# Meishino_v12.net
KiCad netlist of a schematic drawn in EAGLE
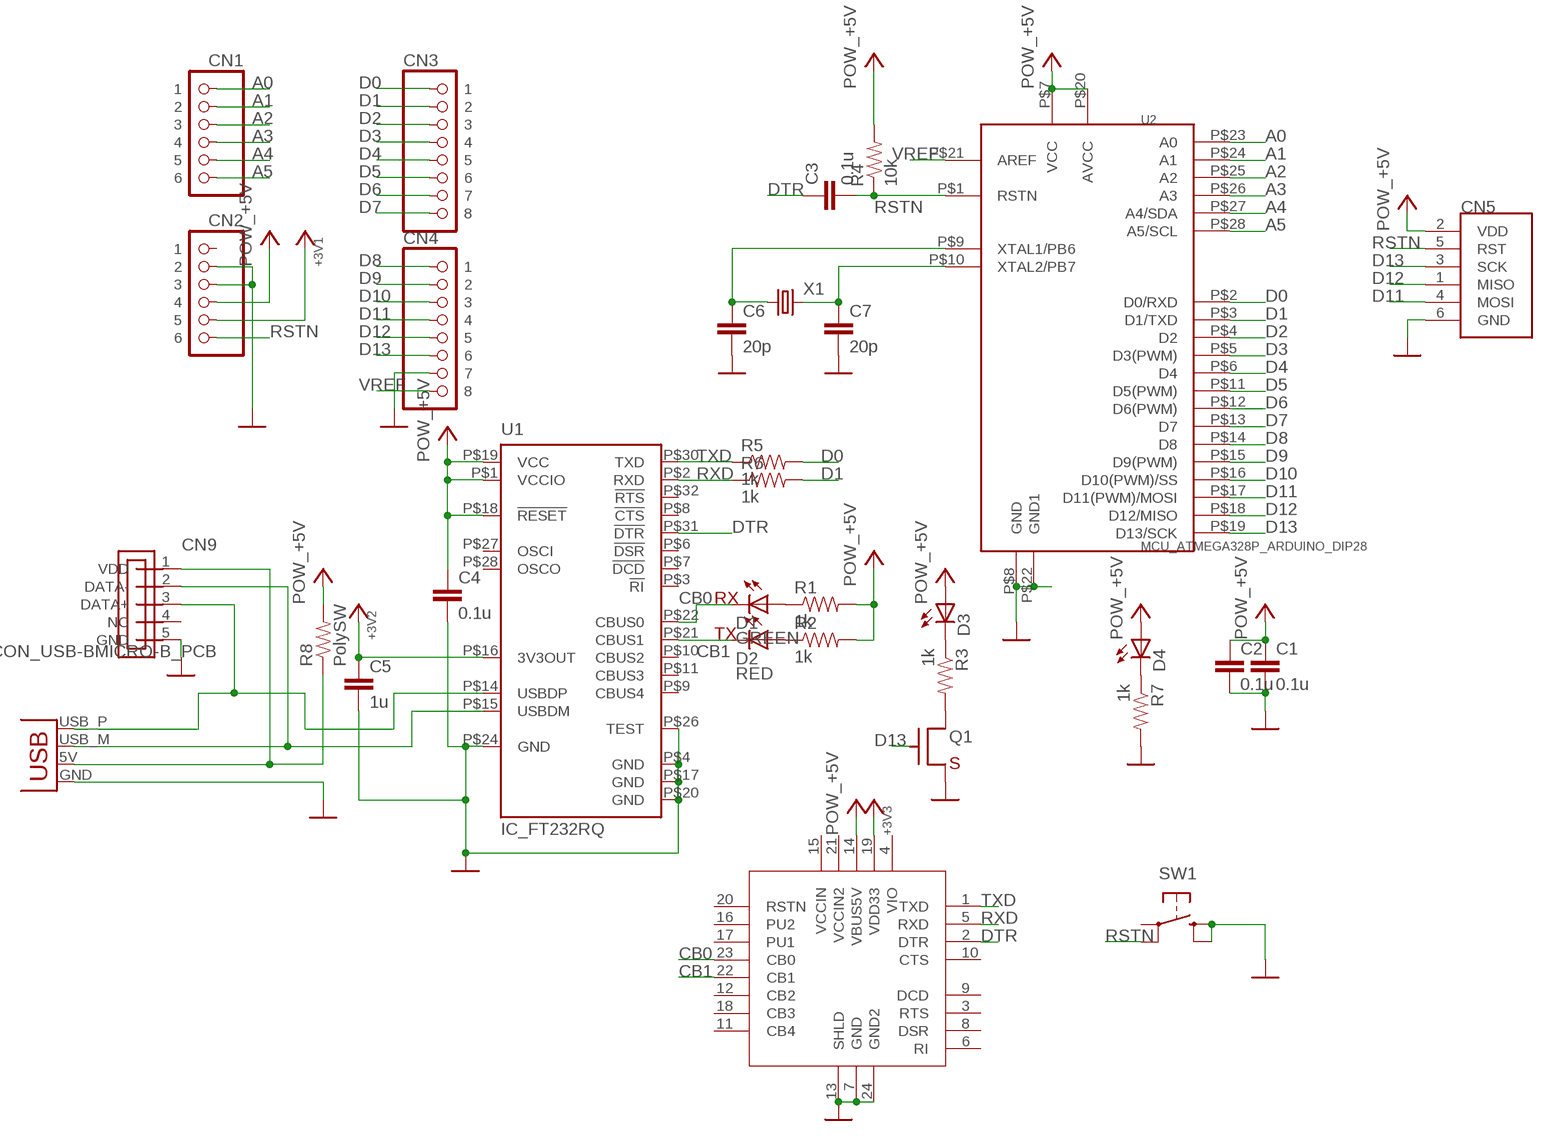
[diagram p0: schematic, sheet 1]

(export (version "E")
  (design (tool "Eeschema 10.0.6"))
  (components
    (comp (ref "C1")
      (value "0.1u")
      (footprint "eagle-import:CAP_TH_5MM_L")
      (libsource (lib "eagle-import") (part "CAPTH_5MML"))
    )
    (comp (ref "C2")
      (value "0.1u")
      (footprint "eagle-import:CAP_TH_5MM_L")
      (libsource (lib "eagle-import") (part "CAPTH_5MML"))
    )
    (comp (ref "C3")
      (value "0.1u")
      (footprint "eagle-import:CAP_TH_5MM_L")
      (libsource (lib "eagle-import") (part "CAPTH_5MML"))
    )
    (comp (ref "C4")
      (value "0.1u")
      (footprint "eagle-import:CAP_TH_5MM_L")
      (libsource (lib "eagle-import") (part "CAPTH_5MML"))
    )
    (comp (ref "C5")
      (value "1u")
      (footprint "eagle-import:CAP_TH_5MM_L")
      (libsource (lib "eagle-import") (part "CAPTH_5MML"))
    )
    (comp (ref "C6")
      (value "20p")
      (footprint "eagle-import:CAP_TH_5MM_L")
      (libsource (lib "eagle-import") (part "CAPTH_5MML"))
    )
    (comp (ref "C7")
      (value "20p")
      (footprint "eagle-import:CAP_TH_5MM_L")
      (libsource (lib "eagle-import") (part "CAPTH_5MML"))
    )
    (comp (ref "CN1")
      (value "CON_PINHD-1X6")
      (footprint "eagle-import:1X06")
      (libsource (lib "eagle-import") (part "CON_PINHD-1X6"))
    )
    (comp (ref "CN2")
      (value "CON_PINHD-1X6")
      (footprint "eagle-import:1X06")
      (libsource (lib "eagle-import") (part "CON_PINHD-1X6"))
    )
    (comp (ref "CN3")
      (value "CON_PINHD-1X8")
      (footprint "eagle-import:1X08")
      (libsource (lib "eagle-import") (part "CON_PINHD-1X8"))
    )
    (comp (ref "CN4")
      (value "CON_PINHD-1X8")
      (footprint "eagle-import:1X08")
      (libsource (lib "eagle-import") (part "CON_PINHD-1X8"))
    )
    (comp (ref "CN5")
      (value "CON_AVRISPTH")
      (footprint "eagle-import:2X03R")
      (libsource (lib "eagle-import") (part "CON_AVRISPTH"))
    )
    (comp (ref "CN9")
      (value "CON_USB-BMICRO-B_PCB")
      (footprint "eagle-import:USB-MICRO-PCB")
      (libsource (lib "eagle-import") (part "CON_USB-BMICRO-B_PCB"))
    )
    (comp (ref "D1")
      (value "GREEN")
      (footprint "eagle-import:SPARKFUN_LED5MM")
      (libsource (lib "eagle-import") (part "LED5MM"))
    )
    (comp (ref "D2")
      (value "RED")
      (footprint "eagle-import:SPARKFUN_LED5MM")
      (libsource (lib "eagle-import") (part "LED5MM"))
    )
    (comp (ref "D3")
      (value "LED5MM")
      (footprint "eagle-import:SPARKFUN_LED5MM")
      (libsource (lib "eagle-import") (part "LED5MM"))
    )
    (comp (ref "D4")
      (value "LED5MM")
      (footprint "eagle-import:SPARKFUN_LED5MM")
      (libsource (lib "eagle-import") (part "LED5MM"))
    )
    (comp (ref "JP2")
      (value "CON_USBPCB")
      (footprint "eagle-import:USB-A-PCB")
      (libsource (lib "eagle-import") (part "CON_USBPCB"))
    )
    (comp (ref "Q1")
      (value "TR_NMOS_2N7000")
      (footprint "eagle-import:TO-92")
      (libsource (lib "eagle-import") (part "TR_NMOS_2N7000"))
    )
    (comp (ref "R1")
      (value "1k")
      (footprint "eagle-import:R_TH_10MM_L")
      (libsource (lib "eagle-import") (part "RESTH_10MML"))
    )
    (comp (ref "R2")
      (value "1k")
      (footprint "eagle-import:R_TH_10MM_L")
      (libsource (lib "eagle-import") (part "RESTH_10MML"))
    )
    (comp (ref "R3")
      (value "1k")
      (footprint "eagle-import:R_TH_10MM_L")
      (libsource (lib "eagle-import") (part "RESTH_10MML"))
    )
    (comp (ref "R4")
      (value "10k")
      (footprint "eagle-import:R_TH_10MM_L")
      (libsource (lib "eagle-import") (part "RESTH_10MML"))
    )
    (comp (ref "R5")
      (value "1k")
      (footprint "eagle-import:R_TH_10MM_L")
      (libsource (lib "eagle-import") (part "RESTH_10MML"))
    )
    (comp (ref "R6")
      (value "1k")
      (footprint "eagle-import:R_TH_10MM_L")
      (libsource (lib "eagle-import") (part "RESTH_10MML"))
    )
    (comp (ref "R7")
      (value "1k")
      (footprint "eagle-import:R_TH_10MM_L")
      (libsource (lib "eagle-import") (part "RESTH_10MML"))
    )
    (comp (ref "R8")
      (value "PolySW")
      (footprint "eagle-import:R_TH_10MM_L")
      (libsource (lib "eagle-import") (part "RESTH_10MML"))
    )
    (comp (ref "SW1")
      (value "SW_TACTTH")
      (footprint "eagle-import:SW_B3F-10XX")
      (fields (field (name "MPN") "B3F-1000"))
      (libsource (lib "eagle-import") (part "SW_TACTTH"))
    )
    (comp (ref "U1")
      (value "IC_FT232RQ")
      (footprint "eagle-import:QFN32")
      (libsource (lib "eagle-import") (part "IC_FT232RQ"))
    )
    (comp (ref "U2")
      (value "MCU_ATMEGA328P_ARDUINO_DIP28")
      (footprint "eagle-import:DIP-28P(300MIL)")
      (libsource (lib "eagle-import") (part "MCU_ATMEGA328P_ARDUINO_DIP28"))
    )
    (comp (ref "U3")
      (value "MOD_AE_FT232_DIP24")
      (footprint "eagle-import:DIP24_600MIL")
      (libsource (lib "eagle-import") (part "MOD_AE_FT232_DIP24"))
    )
    (comp (ref "X1")
      (value "XTAL2HC49US")
      (footprint "eagle-import:HC49US")
      (libsource (lib "eagle-import") (part "XTAL2HC49US"))
    )
  )
  (nets
    (net (code "1") (name "/A0") (class "Default")
      (node (ref "CN1") (pin "1") (pinfunction "1_1") (pintype "passive"))
      (node (ref "U2") (pin "P$23") (pinfunction "A0_P$23") (pintype "bidirectional"))
    )
    (net (code "2") (name "/A1") (class "Default")
      (node (ref "CN1") (pin "2") (pinfunction "2_2") (pintype "passive"))
      (node (ref "U2") (pin "P$24") (pinfunction "A1_P$24") (pintype "bidirectional"))
    )
    (net (code "3") (name "/A2") (class "Default")
      (node (ref "CN1") (pin "3") (pinfunction "3_3") (pintype "passive"))
      (node (ref "U2") (pin "P$25") (pinfunction "A2_P$25") (pintype "bidirectional"))
    )
    (net (code "4") (name "/A3") (class "Default")
      (node (ref "CN1") (pin "4") (pinfunction "4_4") (pintype "passive"))
      (node (ref "U2") (pin "P$26") (pinfunction "A3_P$26") (pintype "bidirectional"))
    )
    (net (code "5") (name "/A4") (class "Default")
      (node (ref "CN1") (pin "5") (pinfunction "5_5") (pintype "passive"))
      (node (ref "U2") (pin "P$27") (pinfunction "A4/SDA_P$27") (pintype "bidirectional"))
    )
    (net (code "6") (name "/A5") (class "Default")
      (node (ref "CN1") (pin "6") (pinfunction "6_6") (pintype "passive"))
      (node (ref "U2") (pin "P$28") (pinfunction "A5/SCL_P$28") (pintype "bidirectional"))
    )
    (net (code "7") (name "/CB0") (class "Default")
      (node (ref "D1") (pin "K") (pinfunction "C_K") (pintype "passive"))
      (node (ref "U1") (pin "P$22") (pinfunction "CBUS0_P$22") (pintype "bidirectional"))
      (node (ref "U3") (pin "23") (pinfunction "CB0_23") (pintype "bidirectional"))
    )
    (net (code "8") (name "/CB1") (class "Default")
      (node (ref "D2") (pin "K") (pinfunction "C_K") (pintype "passive"))
      (node (ref "U1") (pin "P$21") (pinfunction "CBUS1_P$21") (pintype "bidirectional"))
      (node (ref "U3") (pin "22") (pinfunction "CB1_22") (pintype "bidirectional"))
    )
    (net (code "9") (name "/D0") (class "Default")
      (node (ref "CN3") (pin "1") (pinfunction "1_1") (pintype "passive"))
      (node (ref "R5") (pin "2") (pinfunction "2_2") (pintype "passive"))
      (node (ref "U2") (pin "P$2") (pinfunction "D0/RXD_P$2") (pintype "bidirectional"))
    )
    (net (code "10") (name "/D1") (class "Default")
      (node (ref "CN3") (pin "2") (pinfunction "2_2") (pintype "passive"))
      (node (ref "R6") (pin "2") (pinfunction "2_2") (pintype "passive"))
      (node (ref "U2") (pin "P$3") (pinfunction "D1/TXD_P$3") (pintype "bidirectional"))
    )
    (net (code "11") (name "/D2") (class "Default")
      (node (ref "CN3") (pin "3") (pinfunction "3_3") (pintype "passive"))
      (node (ref "U2") (pin "P$4") (pinfunction "D2_P$4") (pintype "bidirectional"))
    )
    (net (code "12") (name "/D3") (class "Default")
      (node (ref "CN3") (pin "4") (pinfunction "4_4") (pintype "passive"))
      (node (ref "U2") (pin "P$5") (pinfunction "D3(PWM)_P$5") (pintype "bidirectional"))
    )
    (net (code "13") (name "/D4") (class "Default")
      (node (ref "CN3") (pin "5") (pinfunction "5_5") (pintype "passive"))
      (node (ref "U2") (pin "P$6") (pinfunction "D4_P$6") (pintype "bidirectional"))
    )
    (net (code "14") (name "/D5") (class "Default")
      (node (ref "CN3") (pin "6") (pinfunction "6_6") (pintype "passive"))
      (node (ref "U2") (pin "P$11") (pinfunction "D5(PWM)_P$11") (pintype "bidirectional"))
    )
    (net (code "15") (name "/D6") (class "Default")
      (node (ref "CN3") (pin "7") (pinfunction "7_7") (pintype "passive"))
      (node (ref "U2") (pin "P$12") (pinfunction "D6(PWM)_P$12") (pintype "bidirectional"))
    )
    (net (code "16") (name "/D7") (class "Default")
      (node (ref "CN3") (pin "8") (pinfunction "8_8") (pintype "passive"))
      (node (ref "U2") (pin "P$13") (pinfunction "D7_P$13") (pintype "bidirectional"))
    )
    (net (code "17") (name "/D8") (class "Default")
      (node (ref "CN4") (pin "1") (pinfunction "1_1") (pintype "passive"))
      (node (ref "U2") (pin "P$14") (pinfunction "D8_P$14") (pintype "bidirectional"))
    )
    (net (code "18") (name "/D9") (class "Default")
      (node (ref "CN4") (pin "2") (pinfunction "2_2") (pintype "passive"))
      (node (ref "U2") (pin "P$15") (pinfunction "D9(PWM)_P$15") (pintype "bidirectional"))
    )
    (net (code "19") (name "/D10") (class "Default")
      (node (ref "CN4") (pin "3") (pinfunction "3_3") (pintype "passive"))
      (node (ref "U2") (pin "P$16") (pinfunction "D10(PWM)/SS_P$16") (pintype "bidirectional"))
    )
    (net (code "20") (name "/D11") (class "Default")
      (node (ref "CN4") (pin "4") (pinfunction "4_4") (pintype "passive"))
      (node (ref "CN5") (pin "4") (pinfunction "MOSI_4") (pintype "bidirectional"))
      (node (ref "U2") (pin "P$17") (pinfunction "D11(PWM)/MOSI_P$17") (pintype "bidirectional"))
    )
    (net (code "21") (name "/D12") (class "Default")
      (node (ref "CN4") (pin "5") (pinfunction "5_5") (pintype "passive"))
      (node (ref "CN5") (pin "1") (pinfunction "MISO_1") (pintype "bidirectional"))
      (node (ref "U2") (pin "P$18") (pinfunction "D12/MISO_P$18") (pintype "bidirectional"))
    )
    (net (code "22") (name "/D13") (class "Default")
      (node (ref "CN4") (pin "6") (pinfunction "6_6") (pintype "passive"))
      (node (ref "CN5") (pin "3") (pinfunction "SCK_3") (pintype "bidirectional"))
      (node (ref "Q1") (pin "2") (pinfunction "G_2") (pintype "bidirectional"))
      (node (ref "U2") (pin "P$19") (pinfunction "D13/SCK_P$19") (pintype "bidirectional"))
    )
    (net (code "23") (name "/DTR") (class "Default")
      (node (ref "C3") (pin "1") (pinfunction "1_1") (pintype "passive"))
      (node (ref "U1") (pin "P$31") (pinfunction "~{DTR}_P$31") (pintype "output"))
      (node (ref "U3") (pin "2") (pinfunction "DTR_2") (pintype "bidirectional"))
    )
    (net (code "24") (name "/RSTN") (class "Default")
      (node (ref "C3") (pin "2") (pinfunction "2_2") (pintype "passive"))
      (node (ref "CN2") (pin "6") (pinfunction "6_6") (pintype "passive"))
      (node (ref "CN5") (pin "5") (pinfunction "RST_5") (pintype "bidirectional"))
      (node (ref "R4") (pin "1") (pinfunction "1_1") (pintype "passive"))
      (node (ref "SW1") (pin "4") (pinfunction "P1_4") (pintype "passive"))
      (node (ref "U2") (pin "P$1") (pinfunction "RSTN_P$1") (pintype "bidirectional"))
    )
    (net (code "25") (name "/RXD") (class "Default")
      (node (ref "R6") (pin "1") (pinfunction "1_1") (pintype "passive"))
      (node (ref "U1") (pin "P$2") (pinfunction "RXD_P$2") (pintype "input"))
      (node (ref "U3") (pin "5") (pinfunction "RXD_5") (pintype "bidirectional"))
    )
    (net (code "26") (name "/TXD") (class "Default")
      (node (ref "R5") (pin "1") (pinfunction "1_1") (pintype "passive"))
      (node (ref "U1") (pin "P$30") (pinfunction "TXD_P$30") (pintype "output"))
      (node (ref "U3") (pin "1") (pinfunction "TXD_1") (pintype "bidirectional"))
    )
    (net (code "27") (name "/VREF") (class "Default")
      (node (ref "CN4") (pin "8") (pinfunction "8_8") (pintype "passive"))
      (node (ref "U2") (pin "P$21") (pinfunction "AREF_P$21") (pintype "bidirectional"))
    )
    (net (code "28") (name "Net-(CN9-DATA+)") (class "Default")
      (node (ref "CN9") (pin "3") (pinfunction "DATA+_3") (pintype "bidirectional"))
      (node (ref "JP2") (pin "USB_P") (pinfunction "D+_USB_P") (pintype "bidirectional"))
      (node (ref "U1") (pin "P$14") (pinfunction "USBDP_P$14") (pintype "bidirectional"))
    )
    (net (code "29") (name "Net-(CN9-DATA-)") (class "Default")
      (node (ref "CN9") (pin "2") (pinfunction "DATA-_2") (pintype "bidirectional"))
      (node (ref "JP2") (pin "USB_M") (pinfunction "D-_USB_M") (pintype "bidirectional"))
      (node (ref "U1") (pin "P$15") (pinfunction "USBDM_P$15") (pintype "bidirectional"))
    )
    (net (code "30") (name "Net-(CN9-VDD)") (class "Default")
      (node (ref "CN9") (pin "1") (pinfunction "VDD_1") (pintype "power_in"))
      (node (ref "JP2") (pin "5V") (pinfunction "VBUS_5V") (pintype "bidirectional"))
      (node (ref "R8") (pin "1") (pinfunction "1_1") (pintype "passive"))
    )
    (net (code "31") (name "Net-(D1-PadA)") (class "Default")
      (node (ref "D1") (pin "A") (pinfunction "A_A") (pintype "passive"))
      (node (ref "R1") (pin "1") (pinfunction "1_1") (pintype "passive"))
    )
    (net (code "32") (name "Net-(D2-PadA)") (class "Default")
      (node (ref "D2") (pin "A") (pinfunction "A_A") (pintype "passive"))
      (node (ref "R2") (pin "1") (pinfunction "1_1") (pintype "passive"))
    )
    (net (code "33") (name "Net-(D3-C)") (class "Default")
      (node (ref "D3") (pin "K") (pinfunction "C_K") (pintype "passive"))
      (node (ref "R3") (pin "1") (pinfunction "1_1") (pintype "passive"))
    )
    (net (code "34") (name "Net-(D4-C)") (class "Default")
      (node (ref "D4") (pin "K") (pinfunction "C_K") (pintype "passive"))
      (node (ref "R7") (pin "1") (pinfunction "1_1") (pintype "passive"))
    )
    (net (code "35") (name "Net-(Q1-D)") (class "Default")
      (node (ref "Q1") (pin "3") (pinfunction "D_3") (pintype "bidirectional"))
      (node (ref "R3") (pin "2") (pinfunction "2_2") (pintype "passive"))
    )
    (net (code "36") (name "Net-(U2-XTAL1{slash}PB6)") (class "Default")
      (node (ref "C6") (pin "1") (pinfunction "1_1") (pintype "passive"))
      (node (ref "U2") (pin "P$9") (pinfunction "XTAL1/PB6_P$9") (pintype "bidirectional"))
      (node (ref "X1") (pin "1") (pinfunction "1_1") (pintype "passive"))
    )
    (net (code "37") (name "Net-(U2-XTAL2{slash}PB7)") (class "Default")
      (node (ref "C7") (pin "1") (pinfunction "1_1") (pintype "passive"))
      (node (ref "U2") (pin "P$10") (pinfunction "XTAL2/PB7_P$10") (pintype "bidirectional"))
      (node (ref "X1") (pin "2") (pinfunction "2_2") (pintype "passive"))
    )
    (net (code "38") (name "POW_+3V3") (class "Default")
      (node (ref "C5") (pin "1") (pinfunction "1_1") (pintype "passive"))
      (node (ref "CN2") (pin "5") (pinfunction "5_5") (pintype "passive"))
      (node (ref "U1") (pin "P$16") (pinfunction "3V3OUT_P$16") (pintype "output"))
      (node (ref "U3") (pin "19") (pinfunction "VDD33_19") (pintype "bidirectional"))
    )
    (net (code "39") (name "POW_+5V") (class "Default")
      (node (ref "C1") (pin "1") (pinfunction "1_1") (pintype "passive"))
      (node (ref "C2") (pin "1") (pinfunction "1_1") (pintype "passive"))
      (node (ref "C4") (pin "1") (pinfunction "1_1") (pintype "passive"))
      (node (ref "CN2") (pin "4") (pinfunction "4_4") (pintype "passive"))
      (node (ref "CN5") (pin "2") (pinfunction "VDD_2") (pintype "bidirectional"))
      (node (ref "D3") (pin "A") (pinfunction "A_A") (pintype "passive"))
      (node (ref "D4") (pin "A") (pinfunction "A_A") (pintype "passive"))
      (node (ref "R1") (pin "2") (pinfunction "2_2") (pintype "passive"))
      (node (ref "R2") (pin "2") (pinfunction "2_2") (pintype "passive"))
      (node (ref "R4") (pin "2") (pinfunction "2_2") (pintype "passive"))
      (node (ref "R8") (pin "2") (pinfunction "2_2") (pintype "passive"))
      (node (ref "U1") (pin "P$1") (pinfunction "VCCIO_P$1") (pintype "power_in"))
      (node (ref "U1") (pin "P$18") (pinfunction "~{RESET}_P$18") (pintype "input"))
      (node (ref "U1") (pin "P$19") (pinfunction "VCC_P$19") (pintype "power_in"))
      (node (ref "U2") (pin "P$20") (pinfunction "AVCC_P$20") (pintype "power_in"))
      (node (ref "U2") (pin "P$7") (pinfunction "VCC_P$7") (pintype "power_in"))
      (node (ref "U3") (pin "14") (pinfunction "VBUS5V_14") (pintype "bidirectional"))
    )
    (net (code "40") (name "POW_GND") (class "Default")
      (node (ref "C1") (pin "2") (pinfunction "2_2") (pintype "passive"))
      (node (ref "C2") (pin "2") (pinfunction "2_2") (pintype "passive"))
      (node (ref "C4") (pin "2") (pinfunction "2_2") (pintype "passive"))
      (node (ref "C5") (pin "2") (pinfunction "2_2") (pintype "passive"))
      (node (ref "C6") (pin "2") (pinfunction "2_2") (pintype "passive"))
      (node (ref "C7") (pin "2") (pinfunction "2_2") (pintype "passive"))
      (node (ref "CN2") (pin "2") (pinfunction "2_2") (pintype "passive"))
      (node (ref "CN2") (pin "3") (pinfunction "3_3") (pintype "passive"))
      (node (ref "CN4") (pin "7") (pinfunction "7_7") (pintype "passive"))
      (node (ref "CN5") (pin "6") (pinfunction "GND_6") (pintype "bidirectional"))
      (node (ref "CN9") (pin "5") (pinfunction "GND_5") (pintype "power_in"))
      (node (ref "JP2") (pin "GND") (pinfunction "GND_GND") (pintype "bidirectional"))
      (node (ref "Q1") (pin "1") (pinfunction "S_1") (pintype "bidirectional"))
      (node (ref "R7") (pin "2") (pinfunction "2_2") (pintype "passive"))
      (node (ref "SW1") (pin "1") (pinfunction "S_1") (pintype "passive"))
      (node (ref "SW1") (pin "2") (pinfunction "S1_2") (pintype "passive"))
      (node (ref "U1") (pin "P$17") (pinfunction "GND_P$17") (pintype "power_in"))
      (node (ref "U1") (pin "P$20") (pinfunction "GND_P$20") (pintype "power_in"))
      (node (ref "U1") (pin "P$24") (pinfunction "GND_P$24") (pintype "power_in"))
      (node (ref "U1") (pin "P$26") (pinfunction "TEST_P$26") (pintype "input"))
      (node (ref "U1") (pin "P$4") (pinfunction "GND_P$4") (pintype "power_in"))
      (node (ref "U2") (pin "P$22") (pinfunction "GND1_P$22") (pintype "power_in"))
      (node (ref "U2") (pin "P$8") (pinfunction "GND_P$8") (pintype "power_in"))
      (node (ref "U3") (pin "13") (pinfunction "SHLD_13") (pintype "bidirectional"))
      (node (ref "U3") (pin "24") (pinfunction "GND2_24") (pintype "bidirectional"))
      (node (ref "U3") (pin "7") (pinfunction "GND_7") (pintype "bidirectional"))
    )
    (net (code "41") (name "unconnected-(CN2-Pad1)") (class "Default")
      (node (ref "CN2") (pin "1") (pinfunction "1_1") (pintype "passive"))
    )
    (net (code "42") (name "unconnected-(CN9-NC-Pad4)") (class "Default")
      (node (ref "CN9") (pin "4") (pinfunction "NC_4") (pintype "bidirectional"))
    )
    (net (code "43") (name "unconnected-(SW1-P-Pad3)") (class "Default")
      (node (ref "SW1") (pin "3") (pinfunction "P_3") (pintype "passive"))
    )
    (net (code "44") (name "unconnected-(U1-CBUS2-PadP$10)") (class "Default")
      (node (ref "U1") (pin "P$10") (pinfunction "CBUS2_P$10") (pintype "bidirectional"))
    )
    (net (code "45") (name "unconnected-(U1-CBUS3-PadP$11)") (class "Default")
      (node (ref "U1") (pin "P$11") (pinfunction "CBUS3_P$11") (pintype "bidirectional"))
    )
    (net (code "46") (name "unconnected-(U1-CBUS4-PadP$9)") (class "Default")
      (node (ref "U1") (pin "P$9") (pinfunction "CBUS4_P$9") (pintype "bidirectional"))
    )
    (net (code "47") (name "unconnected-(U1-OSCI-PadP$27)") (class "Default")
      (node (ref "U1") (pin "P$27") (pinfunction "OSCI_P$27") (pintype "input"))
    )
    (net (code "48") (name "unconnected-(U1-OSCO-PadP$28)") (class "Default")
      (node (ref "U1") (pin "P$28") (pinfunction "OSCO_P$28") (pintype "output"))
    )
    (net (code "49") (name "unconnected-(U1-~{CTS}-PadP$8)") (class "Default")
      (node (ref "U1") (pin "P$8") (pinfunction "~{CTS}_P$8") (pintype "input"))
    )
    (net (code "50") (name "unconnected-(U1-~{DCD}-PadP$7)") (class "Default")
      (node (ref "U1") (pin "P$7") (pinfunction "~{DCD}_P$7") (pintype "input"))
    )
    (net (code "51") (name "unconnected-(U1-~{DSR}-PadP$6)") (class "Default")
      (node (ref "U1") (pin "P$6") (pinfunction "~{DSR}_P$6") (pintype "input"))
    )
    (net (code "52") (name "unconnected-(U1-~{RI}-PadP$3)") (class "Default")
      (node (ref "U1") (pin "P$3") (pinfunction "~{RI}_P$3") (pintype "input"))
    )
    (net (code "53") (name "unconnected-(U1-~{RTS}-PadP$32)") (class "Default")
      (node (ref "U1") (pin "P$32") (pinfunction "~{RTS}_P$32") (pintype "output"))
    )
    (net (code "54") (name "unconnected-(U3-CB2-Pad12)") (class "Default")
      (node (ref "U3") (pin "12") (pinfunction "CB2_12") (pintype "bidirectional"))
    )
    (net (code "55") (name "unconnected-(U3-CB3-Pad18)") (class "Default")
      (node (ref "U3") (pin "18") (pinfunction "CB3_18") (pintype "bidirectional"))
    )
    (net (code "56") (name "unconnected-(U3-CB4-Pad11)") (class "Default")
      (node (ref "U3") (pin "11") (pinfunction "CB4_11") (pintype "bidirectional"))
    )
    (net (code "57") (name "unconnected-(U3-CTS-Pad10)") (class "Default")
      (node (ref "U3") (pin "10") (pinfunction "CTS_10") (pintype "bidirectional"))
    )
    (net (code "58") (name "unconnected-(U3-DCD-Pad9)") (class "Default")
      (node (ref "U3") (pin "9") (pinfunction "DCD_9") (pintype "bidirectional"))
    )
    (net (code "59") (name "unconnected-(U3-DSR-Pad8)") (class "Default")
      (node (ref "U3") (pin "8") (pinfunction "DSR_8") (pintype "bidirectional"))
    )
    (net (code "60") (name "unconnected-(U3-PU1-Pad17)") (class "Default")
      (node (ref "U3") (pin "17") (pinfunction "PU1_17") (pintype "bidirectional"))
    )
    (net (code "61") (name "unconnected-(U3-PU2-Pad16)") (class "Default")
      (node (ref "U3") (pin "16") (pinfunction "PU2_16") (pintype "bidirectional"))
    )
    (net (code "62") (name "unconnected-(U3-RI-Pad6)") (class "Default")
      (node (ref "U3") (pin "6") (pinfunction "RI_6") (pintype "bidirectional"))
    )
    (net (code "63") (name "unconnected-(U3-RSTN-Pad20)") (class "Default")
      (node (ref "U3") (pin "20") (pinfunction "RSTN_20") (pintype "bidirectional"))
    )
    (net (code "64") (name "unconnected-(U3-RTS-Pad3)") (class "Default")
      (node (ref "U3") (pin "3") (pinfunction "RTS_3") (pintype "bidirectional"))
    )
    (net (code "65") (name "unconnected-(U3-VCCIN-Pad15)") (class "Default")
      (node (ref "U3") (pin "15") (pinfunction "VCCIN_15") (pintype "bidirectional"))
    )
    (net (code "66") (name "unconnected-(U3-VCCIN2-Pad21)") (class "Default")
      (node (ref "U3") (pin "21") (pinfunction "VCCIN2_21") (pintype "bidirectional"))
    )
    (net (code "67") (name "unconnected-(U3-VIO-Pad4)") (class "Default")
      (node (ref "U3") (pin "4") (pinfunction "VIO_4") (pintype "bidirectional"))
    )
  )
)
